# FPGA_DDR.net
KiCad netlist of a schematic drawn in Altium Designer
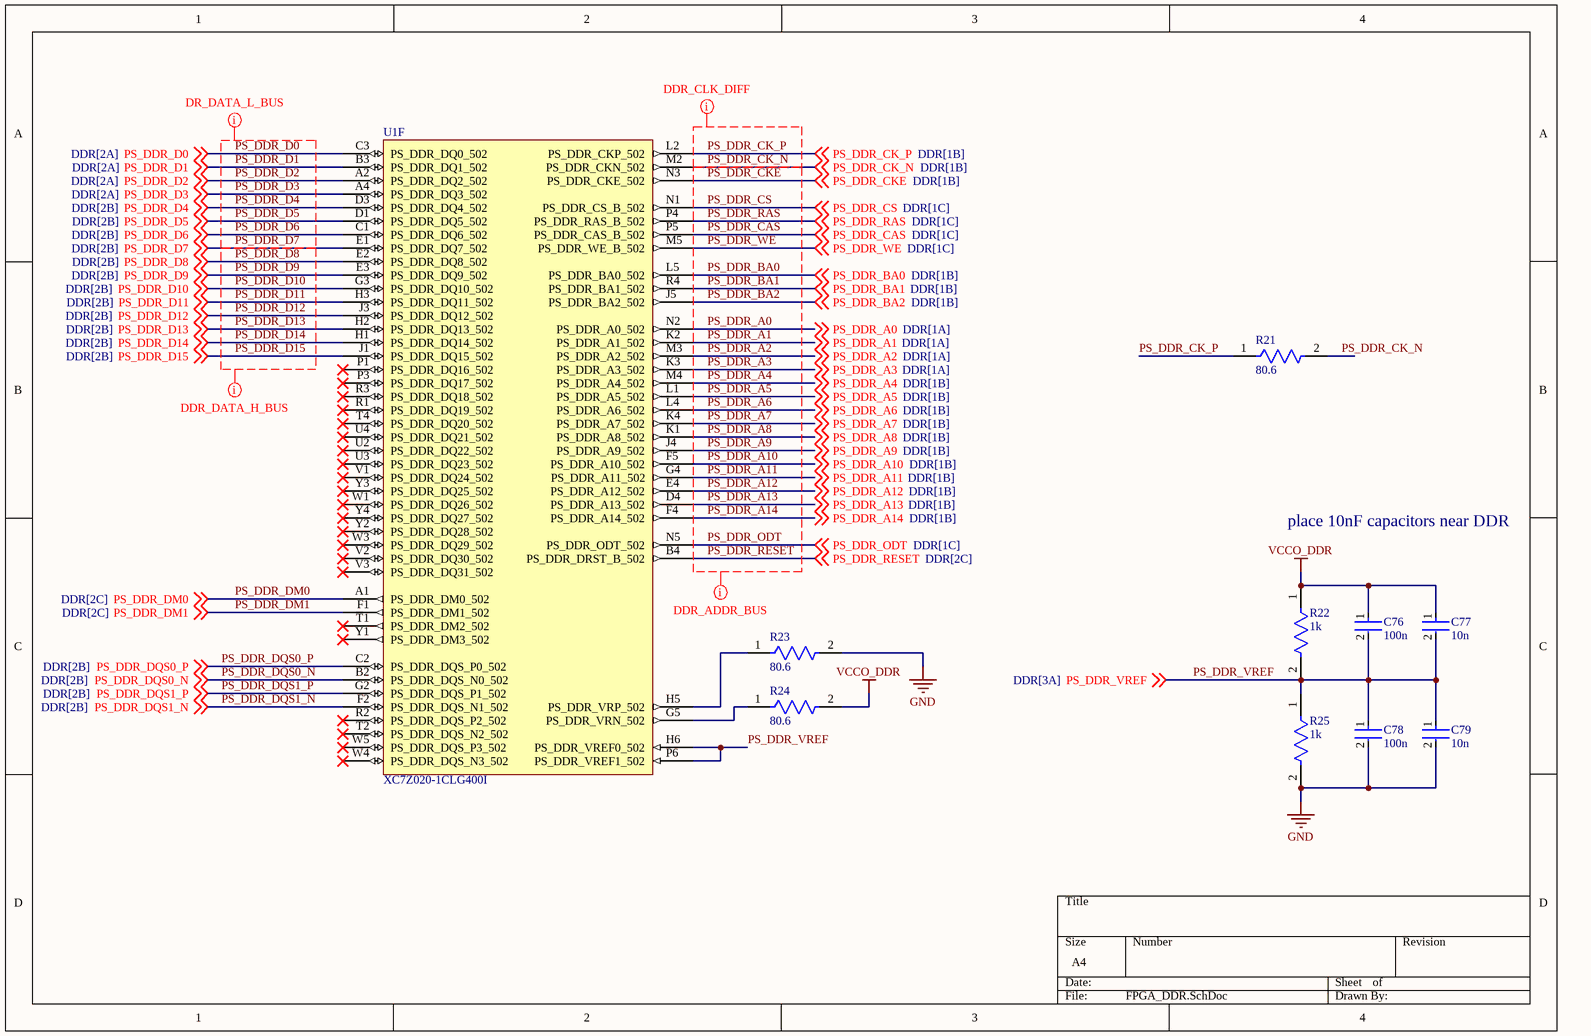
[diagram p0: FPGA_DDR.SchDoc]

(export (version "E")
  (design (tool "Eeschema 10.0.6"))
  (components
    (comp (ref "C76")
      (value "100n")
      (footprint "FP-CC0603-DA-MFG")
      (description "CAP CER 0.1UF 50V X7R 0603")
      (fields (field (name "MANUFACTURER") "YAGEO") (field (name "VOLTAGE") "50 V"))
      (libsource (lib "Altium Content Vault") (part "11868f565c42a9108669ba33697ecf6"))
    )
    (comp (ref "C77")
      (value "10n")
      (footprint "FP-CC0603-DA-MFG")
      (description "CAP CER 10000PF 50V X7R 0603")
      (fields (field (name "TOLERANCE") "0.1") (field (name "MANUFACTURER PART NUMBER") "CC0603KRX7R9BB103"))
      (libsource (lib "Altium Content Vault") (part "11868f565c42a9108669ba33697ecf6"))
    )
    (comp (ref "C78")
      (value "100n")
      (footprint "FP-CC0603-DA-MFG")
      (description "CAP CER 0.1UF 50V X7R 0603")
      (fields (field (name "MANUFACTURER") "YAGEO") (field (name "VOLTAGE") "50 V"))
      (libsource (lib "Altium Content Vault") (part "11868f565c42a9108669ba33697ecf6"))
    )
    (comp (ref "C79")
      (value "10n")
      (footprint "FP-CC0603-DA-MFG")
      (description "CAP CER 10000PF 50V X7R 0603")
      (fields (field (name "TOLERANCE") "0.1") (field (name "MANUFACTURER PART NUMBER") "CC0603KRX7R9BB103"))
      (libsource (lib "Altium Content Vault") (part "11868f565c42a9108669ba33697ecf6"))
    )
    (comp (ref "R21")
      (value "80.6")
      (footprint "FP-RT0402-MFG")
      (description "RT0402 80.6Ω 0.063W 25 ppm/°C 0.10%")
      (fields (field (name "MANUFACTURER") "Yageo"))
      (libsource (lib "Altium Content Vault") (part "1029c3af85768c4190bb7ad29bc67b5"))
    )
    (comp (ref "R22")
      (value "1k")
      (footprint "FP-RC0603-0_55-IPC_C")
      (description "RES 1K OHM 1% 1/10W 0603")
      (fields (field (name "TOLERANCE") "1%"))
      (libsource (lib "Altium Content Vault") (part "1029c3af85768c4190bb7ad29bc67b5"))
    )
    (comp (ref "R23")
      (value "80.6")
      (footprint "FP-RT0603-MFG")
      (description "RES SMD 80.6 OHM 0.1% 1/10W 0603")
      (fields (field (name "TOLERANCE") "0.001") (field (name "MANUFACTURER PART NUMBER") "RT0603BRB0780R6L"))
      (libsource (lib "Altium Content Vault") (part "1029c3af85768c4190bb7ad29bc67b5"))
    )
    (comp (ref "R24")
      (value "80.6")
      (footprint "FP-RT0603-MFG")
      (description "RES SMD 80.6 OHM 0.1% 1/10W 0603")
      (fields (field (name "TOLERANCE") "0.001") (field (name "MANUFACTURER PART NUMBER") "RT0603BRB0780R6L"))
      (libsource (lib "Altium Content Vault") (part "1029c3af85768c4190bb7ad29bc67b5"))
    )
    (comp (ref "R25")
      (value "1k")
      (footprint "FP-RC0603-0_55-IPC_C")
      (description "RES 1K OHM 1% 1/10W 0603")
      (fields (field (name "TOLERANCE") "1%"))
      (libsource (lib "Altium Content Vault") (part "1029c3af85768c4190bb7ad29bc67b5"))
    )
    (comp (ref "U1")
      (value "XC7Z020-1CLG400I")
      (footprint "CLG400")
      (fields (field (name "GENERIC PART NUMBER") "XC7Z020"))
      (libsource (lib "Altium Content Vault") (part "XNLX-XC7Z020-CLG400"))
    )
  )
  (nets
    (net (code "1") (name "GND") (class "Default")
      (node (ref "C78") (pin "2") (pinfunction "2_2") (pintype "passive"))
      (node (ref "C79") (pin "2") (pinfunction "2_2") (pintype "passive"))
      (node (ref "R23") (pin "2") (pinfunction "2_2") (pintype "passive"))
      (node (ref "R25") (pin "2") (pinfunction "2_2") (pintype "passive"))
    )
    (net (code "2") (name "Net-(U1F-PS_DDR_VRN_502)") (class "Default")
      (node (ref "R24") (pin "1") (pinfunction "1_1") (pintype "passive"))
      (node (ref "U1") (pin "G5") (pinfunction "PS_DDR_VRN_502_G5") (pintype "output"))
    )
    (net (code "3") (name "Net-(U1F-PS_DDR_VRP_502)") (class "Default")
      (node (ref "R23") (pin "1") (pinfunction "1_1") (pintype "passive"))
      (node (ref "U1") (pin "H5") (pinfunction "PS_DDR_VRP_502_H5") (pintype "output"))
    )
    (net (code "4") (name "PS_DDR_A0") (class "Default")
      (node (ref "U1") (pin "N2") (pinfunction "PS_DDR_A0_502_N2") (pintype "output"))
    )
    (net (code "5") (name "PS_DDR_A1") (class "Default")
      (node (ref "U1") (pin "K2") (pinfunction "PS_DDR_A1_502_K2") (pintype "output"))
    )
    (net (code "6") (name "PS_DDR_A2") (class "Default")
      (node (ref "U1") (pin "M3") (pinfunction "PS_DDR_A2_502_M3") (pintype "output"))
    )
    (net (code "7") (name "PS_DDR_A3") (class "Default")
      (node (ref "U1") (pin "K3") (pinfunction "PS_DDR_A3_502_K3") (pintype "output"))
    )
    (net (code "8") (name "PS_DDR_A4") (class "Default")
      (node (ref "U1") (pin "M4") (pinfunction "PS_DDR_A4_502_M4") (pintype "output"))
    )
    (net (code "9") (name "PS_DDR_A5") (class "Default")
      (node (ref "U1") (pin "L1") (pinfunction "PS_DDR_A5_502_L1") (pintype "output"))
    )
    (net (code "10") (name "PS_DDR_A6") (class "Default")
      (node (ref "U1") (pin "L4") (pinfunction "PS_DDR_A6_502_L4") (pintype "output"))
    )
    (net (code "11") (name "PS_DDR_A7") (class "Default")
      (node (ref "U1") (pin "K4") (pinfunction "PS_DDR_A7_502_K4") (pintype "output"))
    )
    (net (code "12") (name "PS_DDR_A8") (class "Default")
      (node (ref "U1") (pin "K1") (pinfunction "PS_DDR_A8_502_K1") (pintype "output"))
    )
    (net (code "13") (name "PS_DDR_A9") (class "Default")
      (node (ref "U1") (pin "J4") (pinfunction "PS_DDR_A9_502_J4") (pintype "output"))
    )
    (net (code "14") (name "PS_DDR_A10") (class "Default")
      (node (ref "U1") (pin "F5") (pinfunction "PS_DDR_A10_502_F5") (pintype "output"))
    )
    (net (code "15") (name "PS_DDR_A11") (class "Default")
      (node (ref "U1") (pin "G4") (pinfunction "PS_DDR_A11_502_G4") (pintype "output"))
    )
    (net (code "16") (name "PS_DDR_A12") (class "Default")
      (node (ref "U1") (pin "E4") (pinfunction "PS_DDR_A12_502_E4") (pintype "output"))
    )
    (net (code "17") (name "PS_DDR_A13") (class "Default")
      (node (ref "U1") (pin "D4") (pinfunction "PS_DDR_A13_502_D4") (pintype "output"))
    )
    (net (code "18") (name "PS_DDR_A14") (class "Default")
      (node (ref "U1") (pin "F4") (pinfunction "PS_DDR_A14_502_F4") (pintype "output"))
    )
    (net (code "19") (name "PS_DDR_BA0") (class "Default")
      (node (ref "U1") (pin "L5") (pinfunction "PS_DDR_BA0_502_L5") (pintype "output"))
    )
    (net (code "20") (name "PS_DDR_BA1") (class "Default")
      (node (ref "U1") (pin "R4") (pinfunction "PS_DDR_BA1_502_R4") (pintype "output"))
    )
    (net (code "21") (name "PS_DDR_BA2") (class "Default")
      (node (ref "U1") (pin "J5") (pinfunction "PS_DDR_BA2_502_J5") (pintype "output"))
    )
    (net (code "22") (name "PS_DDR_CAS") (class "Default")
      (node (ref "U1") (pin "P5") (pinfunction "PS_DDR_CAS_B_502_P5") (pintype "output"))
    )
    (net (code "23") (name "PS_DDR_CKE") (class "Default")
      (node (ref "U1") (pin "N3") (pinfunction "PS_DDR_CKE_502_N3") (pintype "output"))
    )
    (net (code "24") (name "PS_DDR_CK_N") (class "Default")
      (node (ref "R21") (pin "2") (pinfunction "2_2") (pintype "passive"))
      (node (ref "U1") (pin "M2") (pinfunction "PS_DDR_CKN_502_M2") (pintype "output"))
    )
    (net (code "25") (name "PS_DDR_CK_P") (class "Default")
      (node (ref "R21") (pin "1") (pinfunction "1_1") (pintype "passive"))
      (node (ref "U1") (pin "L2") (pinfunction "PS_DDR_CKP_502_L2") (pintype "output"))
    )
    (net (code "26") (name "PS_DDR_CS") (class "Default")
      (node (ref "U1") (pin "N1") (pinfunction "PS_DDR_CS_B_502_N1") (pintype "output"))
    )
    (net (code "27") (name "PS_DDR_D0") (class "Default")
      (node (ref "U1") (pin "C3") (pinfunction "PS_DDR_DQ0_502_C3") (pintype "bidirectional"))
    )
    (net (code "28") (name "PS_DDR_D1") (class "Default")
      (node (ref "U1") (pin "B3") (pinfunction "PS_DDR_DQ1_502_B3") (pintype "bidirectional"))
    )
    (net (code "29") (name "PS_DDR_D2") (class "Default")
      (node (ref "U1") (pin "A2") (pinfunction "PS_DDR_DQ2_502_A2") (pintype "bidirectional"))
    )
    (net (code "30") (name "PS_DDR_D3") (class "Default")
      (node (ref "U1") (pin "A4") (pinfunction "PS_DDR_DQ3_502_A4") (pintype "bidirectional"))
    )
    (net (code "31") (name "PS_DDR_D4") (class "Default")
      (node (ref "U1") (pin "D3") (pinfunction "PS_DDR_DQ4_502_D3") (pintype "bidirectional"))
    )
    (net (code "32") (name "PS_DDR_D5") (class "Default")
      (node (ref "U1") (pin "D1") (pinfunction "PS_DDR_DQ5_502_D1") (pintype "bidirectional"))
    )
    (net (code "33") (name "PS_DDR_D6") (class "Default")
      (node (ref "U1") (pin "C1") (pinfunction "PS_DDR_DQ6_502_C1") (pintype "bidirectional"))
    )
    (net (code "34") (name "PS_DDR_D7") (class "Default")
      (node (ref "U1") (pin "E1") (pinfunction "PS_DDR_DQ7_502_E1") (pintype "bidirectional"))
    )
    (net (code "35") (name "PS_DDR_D8") (class "Default")
      (node (ref "U1") (pin "E2") (pinfunction "PS_DDR_DQ8_502_E2") (pintype "bidirectional"))
    )
    (net (code "36") (name "PS_DDR_D9") (class "Default")
      (node (ref "U1") (pin "E3") (pinfunction "PS_DDR_DQ9_502_E3") (pintype "bidirectional"))
    )
    (net (code "37") (name "PS_DDR_D10") (class "Default")
      (node (ref "U1") (pin "G3") (pinfunction "PS_DDR_DQ10_502_G3") (pintype "bidirectional"))
    )
    (net (code "38") (name "PS_DDR_D11") (class "Default")
      (node (ref "U1") (pin "H3") (pinfunction "PS_DDR_DQ11_502_H3") (pintype "bidirectional"))
    )
    (net (code "39") (name "PS_DDR_D12") (class "Default")
      (node (ref "U1") (pin "J3") (pinfunction "PS_DDR_DQ12_502_J3") (pintype "bidirectional"))
    )
    (net (code "40") (name "PS_DDR_D13") (class "Default")
      (node (ref "U1") (pin "H2") (pinfunction "PS_DDR_DQ13_502_H2") (pintype "bidirectional"))
    )
    (net (code "41") (name "PS_DDR_D14") (class "Default")
      (node (ref "U1") (pin "H1") (pinfunction "PS_DDR_DQ14_502_H1") (pintype "bidirectional"))
    )
    (net (code "42") (name "PS_DDR_D15") (class "Default")
      (node (ref "U1") (pin "J1") (pinfunction "PS_DDR_DQ15_502_J1") (pintype "bidirectional"))
    )
    (net (code "43") (name "PS_DDR_DM0") (class "Default")
      (node (ref "U1") (pin "A1") (pinfunction "PS_DDR_DM0_502_A1") (pintype "output"))
    )
    (net (code "44") (name "PS_DDR_DM1") (class "Default")
      (node (ref "U1") (pin "F1") (pinfunction "PS_DDR_DM1_502_F1") (pintype "output"))
    )
    (net (code "45") (name "PS_DDR_DQS0_N") (class "Default")
      (node (ref "U1") (pin "B2") (pinfunction "PS_DDR_DQS_N0_502_B2") (pintype "bidirectional"))
    )
    (net (code "46") (name "PS_DDR_DQS0_P") (class "Default")
      (node (ref "U1") (pin "C2") (pinfunction "PS_DDR_DQS_P0_502_C2") (pintype "bidirectional"))
    )
    (net (code "47") (name "PS_DDR_DQS1_N") (class "Default")
      (node (ref "U1") (pin "F2") (pinfunction "PS_DDR_DQS_N1_502_F2") (pintype "bidirectional"))
    )
    (net (code "48") (name "PS_DDR_DQS1_P") (class "Default")
      (node (ref "U1") (pin "G2") (pinfunction "PS_DDR_DQS_P1_502_G2") (pintype "bidirectional"))
    )
    (net (code "49") (name "PS_DDR_ODT") (class "Default")
      (node (ref "U1") (pin "N5") (pinfunction "PS_DDR_ODT_502_N5") (pintype "output"))
    )
    (net (code "50") (name "PS_DDR_RAS") (class "Default")
      (node (ref "U1") (pin "P4") (pinfunction "PS_DDR_RAS_B_502_P4") (pintype "output"))
    )
    (net (code "51") (name "PS_DDR_RESET") (class "Default")
      (node (ref "U1") (pin "B4") (pinfunction "PS_DDR_DRST_B_502_B4") (pintype "output"))
    )
    (net (code "52") (name "PS_DDR_VREF") (class "Default")
      (node (ref "C76") (pin "2") (pinfunction "2_2") (pintype "passive"))
      (node (ref "C77") (pin "2") (pinfunction "2_2") (pintype "passive"))
      (node (ref "C78") (pin "1") (pinfunction "1_1") (pintype "passive"))
      (node (ref "C79") (pin "1") (pinfunction "1_1") (pintype "passive"))
      (node (ref "R22") (pin "2") (pinfunction "2_2") (pintype "passive"))
      (node (ref "R25") (pin "1") (pinfunction "1_1") (pintype "passive"))
      (node (ref "U1") (pin "H6") (pinfunction "PS_DDR_VREF0_502_H6") (pintype "input"))
      (node (ref "U1") (pin "P6") (pinfunction "PS_DDR_VREF1_502_P6") (pintype "input"))
    )
    (net (code "53") (name "PS_DDR_WE") (class "Default")
      (node (ref "U1") (pin "M5") (pinfunction "PS_DDR_WE_B_502_M5") (pintype "output"))
    )
    (net (code "54") (name "VCCO_DDR") (class "Default")
      (node (ref "C76") (pin "1") (pinfunction "1_1") (pintype "passive"))
      (node (ref "C77") (pin "1") (pinfunction "1_1") (pintype "passive"))
      (node (ref "R22") (pin "1") (pinfunction "1_1") (pintype "passive"))
      (node (ref "R24") (pin "2") (pinfunction "2_2") (pintype "passive"))
    )
    (net (code "55") (name "unconnected-(U1F-PS_DDR_DM2_502-PadT1)") (class "Default")
      (node (ref "U1") (pin "T1") (pinfunction "PS_DDR_DM2_502_T1") (pintype "output+no_connect"))
    )
    (net (code "56") (name "unconnected-(U1F-PS_DDR_DM3_502-PadY1)") (class "Default")
      (node (ref "U1") (pin "Y1") (pinfunction "PS_DDR_DM3_502_Y1") (pintype "output+no_connect"))
    )
    (net (code "57") (name "unconnected-(U1F-PS_DDR_DQ16_502-PadP1)") (class "Default")
      (node (ref "U1") (pin "P1") (pinfunction "PS_DDR_DQ16_502_P1") (pintype "bidirectional+no_connect"))
    )
    (net (code "58") (name "unconnected-(U1F-PS_DDR_DQ17_502-PadP3)") (class "Default")
      (node (ref "U1") (pin "P3") (pinfunction "PS_DDR_DQ17_502_P3") (pintype "bidirectional+no_connect"))
    )
    (net (code "59") (name "unconnected-(U1F-PS_DDR_DQ18_502-PadR3)") (class "Default")
      (node (ref "U1") (pin "R3") (pinfunction "PS_DDR_DQ18_502_R3") (pintype "bidirectional+no_connect"))
    )
    (net (code "60") (name "unconnected-(U1F-PS_DDR_DQ19_502-PadR1)") (class "Default")
      (node (ref "U1") (pin "R1") (pinfunction "PS_DDR_DQ19_502_R1") (pintype "bidirectional+no_connect"))
    )
    (net (code "61") (name "unconnected-(U1F-PS_DDR_DQ20_502-PadT4)") (class "Default")
      (node (ref "U1") (pin "T4") (pinfunction "PS_DDR_DQ20_502_T4") (pintype "bidirectional+no_connect"))
    )
    (net (code "62") (name "unconnected-(U1F-PS_DDR_DQ21_502-PadU4)") (class "Default")
      (node (ref "U1") (pin "U4") (pinfunction "PS_DDR_DQ21_502_U4") (pintype "bidirectional+no_connect"))
    )
    (net (code "63") (name "unconnected-(U1F-PS_DDR_DQ22_502-PadU2)") (class "Default")
      (node (ref "U1") (pin "U2") (pinfunction "PS_DDR_DQ22_502_U2") (pintype "bidirectional+no_connect"))
    )
    (net (code "64") (name "unconnected-(U1F-PS_DDR_DQ23_502-PadU3)") (class "Default")
      (node (ref "U1") (pin "U3") (pinfunction "PS_DDR_DQ23_502_U3") (pintype "bidirectional+no_connect"))
    )
    (net (code "65") (name "unconnected-(U1F-PS_DDR_DQ24_502-PadV1)") (class "Default")
      (node (ref "U1") (pin "V1") (pinfunction "PS_DDR_DQ24_502_V1") (pintype "bidirectional+no_connect"))
    )
    (net (code "66") (name "unconnected-(U1F-PS_DDR_DQ25_502-PadY3)") (class "Default")
      (node (ref "U1") (pin "Y3") (pinfunction "PS_DDR_DQ25_502_Y3") (pintype "bidirectional+no_connect"))
    )
    (net (code "67") (name "unconnected-(U1F-PS_DDR_DQ26_502-PadW1)") (class "Default")
      (node (ref "U1") (pin "W1") (pinfunction "PS_DDR_DQ26_502_W1") (pintype "bidirectional+no_connect"))
    )
    (net (code "68") (name "unconnected-(U1F-PS_DDR_DQ27_502-PadY4)") (class "Default")
      (node (ref "U1") (pin "Y4") (pinfunction "PS_DDR_DQ27_502_Y4") (pintype "bidirectional+no_connect"))
    )
    (net (code "69") (name "unconnected-(U1F-PS_DDR_DQ28_502-PadY2)") (class "Default")
      (node (ref "U1") (pin "Y2") (pinfunction "PS_DDR_DQ28_502_Y2") (pintype "bidirectional+no_connect"))
    )
    (net (code "70") (name "unconnected-(U1F-PS_DDR_DQ29_502-PadW3)") (class "Default")
      (node (ref "U1") (pin "W3") (pinfunction "PS_DDR_DQ29_502_W3") (pintype "bidirectional+no_connect"))
    )
    (net (code "71") (name "unconnected-(U1F-PS_DDR_DQ30_502-PadV2)") (class "Default")
      (node (ref "U1") (pin "V2") (pinfunction "PS_DDR_DQ30_502_V2") (pintype "bidirectional+no_connect"))
    )
    (net (code "72") (name "unconnected-(U1F-PS_DDR_DQ31_502-PadV3)") (class "Default")
      (node (ref "U1") (pin "V3") (pinfunction "PS_DDR_DQ31_502_V3") (pintype "bidirectional+no_connect"))
    )
    (net (code "73") (name "unconnected-(U1F-PS_DDR_DQS_N2_502-PadT2)") (class "Default")
      (node (ref "U1") (pin "T2") (pinfunction "PS_DDR_DQS_N2_502_T2") (pintype "bidirectional+no_connect"))
    )
    (net (code "74") (name "unconnected-(U1F-PS_DDR_DQS_N3_502-PadW4)") (class "Default")
      (node (ref "U1") (pin "W4") (pinfunction "PS_DDR_DQS_N3_502_W4") (pintype "bidirectional+no_connect"))
    )
    (net (code "75") (name "unconnected-(U1F-PS_DDR_DQS_P2_502-PadR2)") (class "Default")
      (node (ref "U1") (pin "R2") (pinfunction "PS_DDR_DQS_P2_502_R2") (pintype "bidirectional+no_connect"))
    )
    (net (code "76") (name "unconnected-(U1F-PS_DDR_DQS_P3_502-PadW5)") (class "Default")
      (node (ref "U1") (pin "W5") (pinfunction "PS_DDR_DQS_P3_502_W5") (pintype "bidirectional+no_connect"))
    )
  )
)
